# TouScruino-ui1-v0.net
KiCad netlist of a schematic drawn in EAGLE
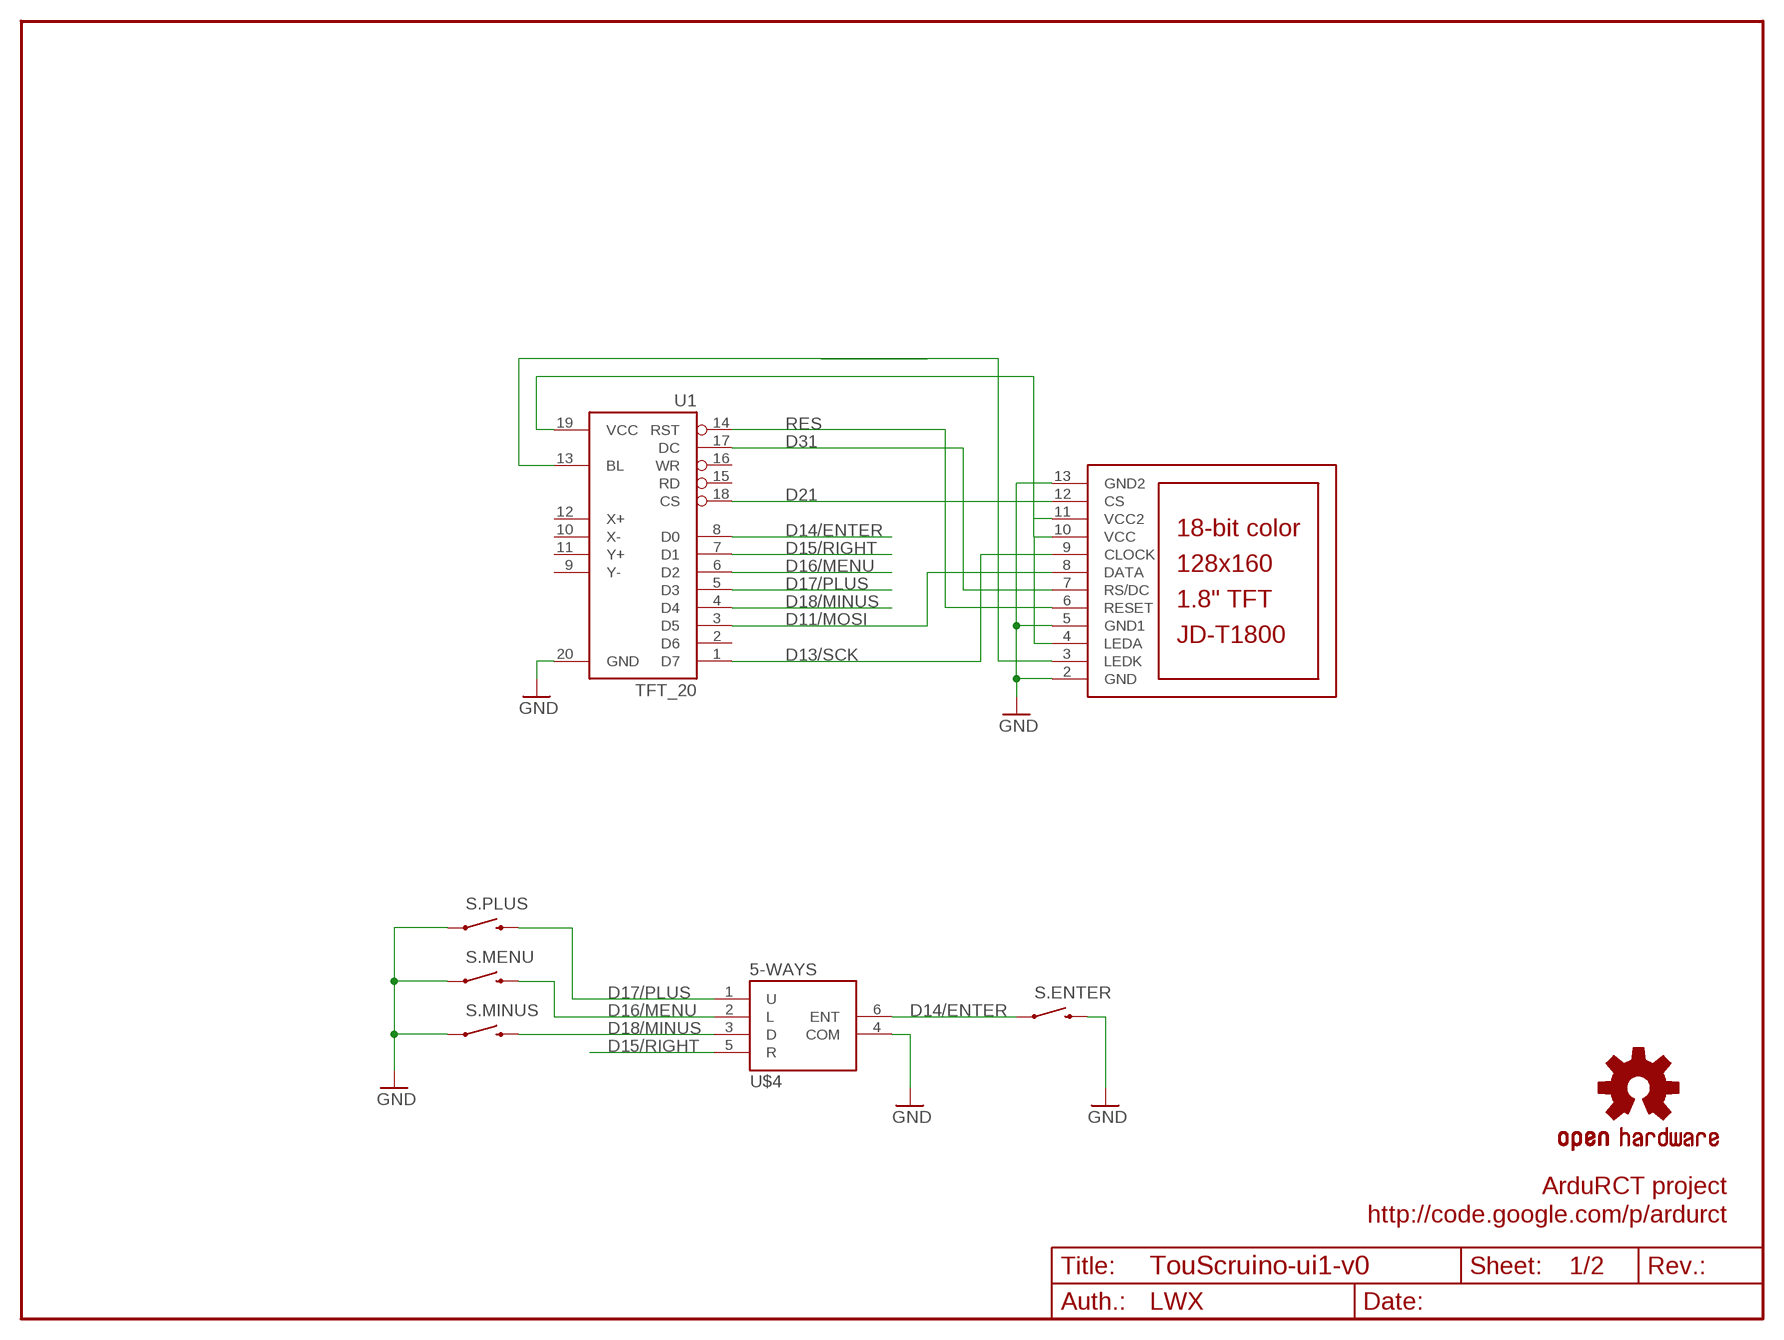
[diagram p0: schematic, sheet 1]

(export (version "E")
  (design (tool "Eeschema 10.0.6"))
  (components
    (comp (ref "LCD1")
      (value "JD-T1800")
      (footprint "eagle-import:JD-T1800")
      (libsource (lib "eagle-import") (part "JD-T1800"))
    )
    (comp (ref "S.ENTER")
      (value "SWITCH_SMD")
      (footprint "eagle-import:TACTILE_SWITCH_SMD")
      (libsource (lib "eagle-import") (part "SWITCH_SMD"))
    )
    (comp (ref "S.MENU")
      (value "SWITCH_SMD")
      (footprint "eagle-import:TACTILE_SWITCH_SMD")
      (libsource (lib "eagle-import") (part "SWITCH_SMD"))
    )
    (comp (ref "S.MINUS")
      (value "SWITCH_SMD")
      (footprint "eagle-import:TACTILE_SWITCH_SMD")
      (libsource (lib "eagle-import") (part "SWITCH_SMD"))
    )
    (comp (ref "S.PLUS")
      (value "SWITCH_SMD")
      (footprint "eagle-import:TACTILE_SWITCH_SMD")
      (libsource (lib "eagle-import") (part "SWITCH_SMD"))
    )
    (comp (ref "U$3")
      (value "OSHW-LOGOM")
      (footprint "eagle-import:OSHW-LOGO-M")
      (libsource (lib "eagle-import") (part "OSHW-LOGOM"))
    )
    (comp (ref "U$4")
      (value "5-WAYS")
      (footprint "eagle-import:5-WAYS_ALPS")
      (libsource (lib "eagle-import") (part "5-WAYS"))
    )
    (comp (ref "U1")
      (value "TFT_20")
      (footprint "eagle-import:TFT_20")
      (libsource (lib "eagle-import") (part "TFT_20"))
    )
  )
  (nets
    (net (code "1") (name "/D11{slash}MOSI") (class "Default")
      (node (ref "LCD1") (pin "8") (pinfunction "DATA_8") (pintype "bidirectional"))
      (node (ref "U1") (pin "3") (pinfunction "D5_3") (pintype "bidirectional"))
    )
    (net (code "2") (name "/D13{slash}SCK") (class "Default")
      (node (ref "LCD1") (pin "9") (pinfunction "CLOCK_9") (pintype "input"))
      (node (ref "U1") (pin "1") (pinfunction "D7_1") (pintype "bidirectional"))
    )
    (net (code "3") (name "/D14{slash}ENTER") (class "Default")
      (node (ref "S.ENTER") (pin "1") (pinfunction "1_1") (pintype "passive"))
      (node (ref "U$4") (pin "6") (pinfunction "ENT_6") (pintype "bidirectional"))
      (node (ref "U1") (pin "8") (pinfunction "D0_8") (pintype "bidirectional"))
    )
    (net (code "4") (name "/D15{slash}RIGHT") (class "Default")
      (node (ref "U$4") (pin "5") (pinfunction "R_5") (pintype "bidirectional"))
      (node (ref "U1") (pin "7") (pinfunction "D1_7") (pintype "bidirectional"))
    )
    (net (code "5") (name "/D16{slash}MENU") (class "Default")
      (node (ref "S.MENU") (pin "3") (pinfunction "2_3") (pintype "passive"))
      (node (ref "U$4") (pin "2") (pinfunction "L_2") (pintype "bidirectional"))
      (node (ref "U1") (pin "6") (pinfunction "D2_6") (pintype "bidirectional"))
    )
    (net (code "6") (name "/D17{slash}PLUS") (class "Default")
      (node (ref "S.PLUS") (pin "3") (pinfunction "2_3") (pintype "passive"))
      (node (ref "U$4") (pin "1") (pinfunction "U_1") (pintype "bidirectional"))
      (node (ref "U1") (pin "5") (pinfunction "D3_5") (pintype "bidirectional"))
    )
    (net (code "7") (name "/D18{slash}MINUS") (class "Default")
      (node (ref "S.MINUS") (pin "3") (pinfunction "2_3") (pintype "passive"))
      (node (ref "U$4") (pin "3") (pinfunction "D_3") (pintype "bidirectional"))
      (node (ref "U1") (pin "4") (pinfunction "D4_4") (pintype "bidirectional"))
    )
    (net (code "8") (name "/D21") (class "Default")
      (node (ref "LCD1") (pin "12") (pinfunction "CS_12") (pintype "input"))
      (node (ref "U1") (pin "18") (pinfunction "CS_18") (pintype "bidirectional"))
    )
    (net (code "9") (name "/D31") (class "Default")
      (node (ref "LCD1") (pin "7") (pinfunction "RS/DC_7") (pintype "input"))
      (node (ref "U1") (pin "17") (pinfunction "DC_17") (pintype "bidirectional"))
    )
    (net (code "10") (name "/RES") (class "Default")
      (node (ref "LCD1") (pin "6") (pinfunction "RESET_6") (pintype "input"))
      (node (ref "U1") (pin "14") (pinfunction "RST_14") (pintype "bidirectional"))
    )
    (net (code "11") (name "GND") (class "Default")
      (node (ref "LCD1") (pin "13") (pinfunction "GND2_13") (pintype "power_in"))
      (node (ref "LCD1") (pin "2") (pinfunction "GND_2") (pintype "power_in"))
      (node (ref "LCD1") (pin "5") (pinfunction "GND1_5") (pintype "power_in"))
      (node (ref "S.ENTER") (pin "3") (pinfunction "2_3") (pintype "passive"))
      (node (ref "S.MENU") (pin "1") (pinfunction "1_1") (pintype "passive"))
      (node (ref "S.MINUS") (pin "1") (pinfunction "1_1") (pintype "passive"))
      (node (ref "S.PLUS") (pin "1") (pinfunction "1_1") (pintype "passive"))
      (node (ref "U$4") (pin "4") (pinfunction "COM_4") (pintype "bidirectional"))
      (node (ref "U1") (pin "20") (pinfunction "GND_20") (pintype "bidirectional"))
    )
    (net (code "12") (name "Net-(LCD1-LEDA)") (class "Default")
      (node (ref "LCD1") (pin "10") (pinfunction "VCC_10") (pintype "power_in"))
      (node (ref "LCD1") (pin "11") (pinfunction "VCC2_11") (pintype "power_in"))
      (node (ref "LCD1") (pin "4") (pinfunction "LEDA_4") (pintype "input"))
      (node (ref "U1") (pin "19") (pinfunction "VCC_19") (pintype "bidirectional"))
    )
    (net (code "13") (name "Net-(LCD1-LEDK)") (class "Default")
      (node (ref "LCD1") (pin "3") (pinfunction "LEDK_3") (pintype "input"))
      (node (ref "U1") (pin "13") (pinfunction "BL_13") (pintype "bidirectional"))
    )
    (net (code "14") (name "unconnected-(U1-D6-Pad2)") (class "Default")
      (node (ref "U1") (pin "2") (pinfunction "D6_2") (pintype "bidirectional"))
    )
    (net (code "15") (name "unconnected-(U1-RD-Pad15)") (class "Default")
      (node (ref "U1") (pin "15") (pinfunction "RD_15") (pintype "bidirectional"))
    )
    (net (code "16") (name "unconnected-(U1-WR-Pad16)") (class "Default")
      (node (ref "U1") (pin "16") (pinfunction "WR_16") (pintype "bidirectional"))
    )
    (net (code "17") (name "unconnected-(U1-X+-Pad12)") (class "Default")
      (node (ref "U1") (pin "12") (pinfunction "X+_12") (pintype "bidirectional"))
    )
    (net (code "18") (name "unconnected-(U1-X--Pad10)") (class "Default")
      (node (ref "U1") (pin "10") (pinfunction "X-_10") (pintype "bidirectional"))
    )
    (net (code "19") (name "unconnected-(U1-Y+-Pad11)") (class "Default")
      (node (ref "U1") (pin "11") (pinfunction "Y+_11") (pintype "bidirectional"))
    )
    (net (code "20") (name "unconnected-(U1-Y--Pad9)") (class "Default")
      (node (ref "U1") (pin "9") (pinfunction "Y-_9") (pintype "bidirectional"))
    )
  )
)
